# IDC.net
KiCad netlist of a schematic drawn in EAGLE
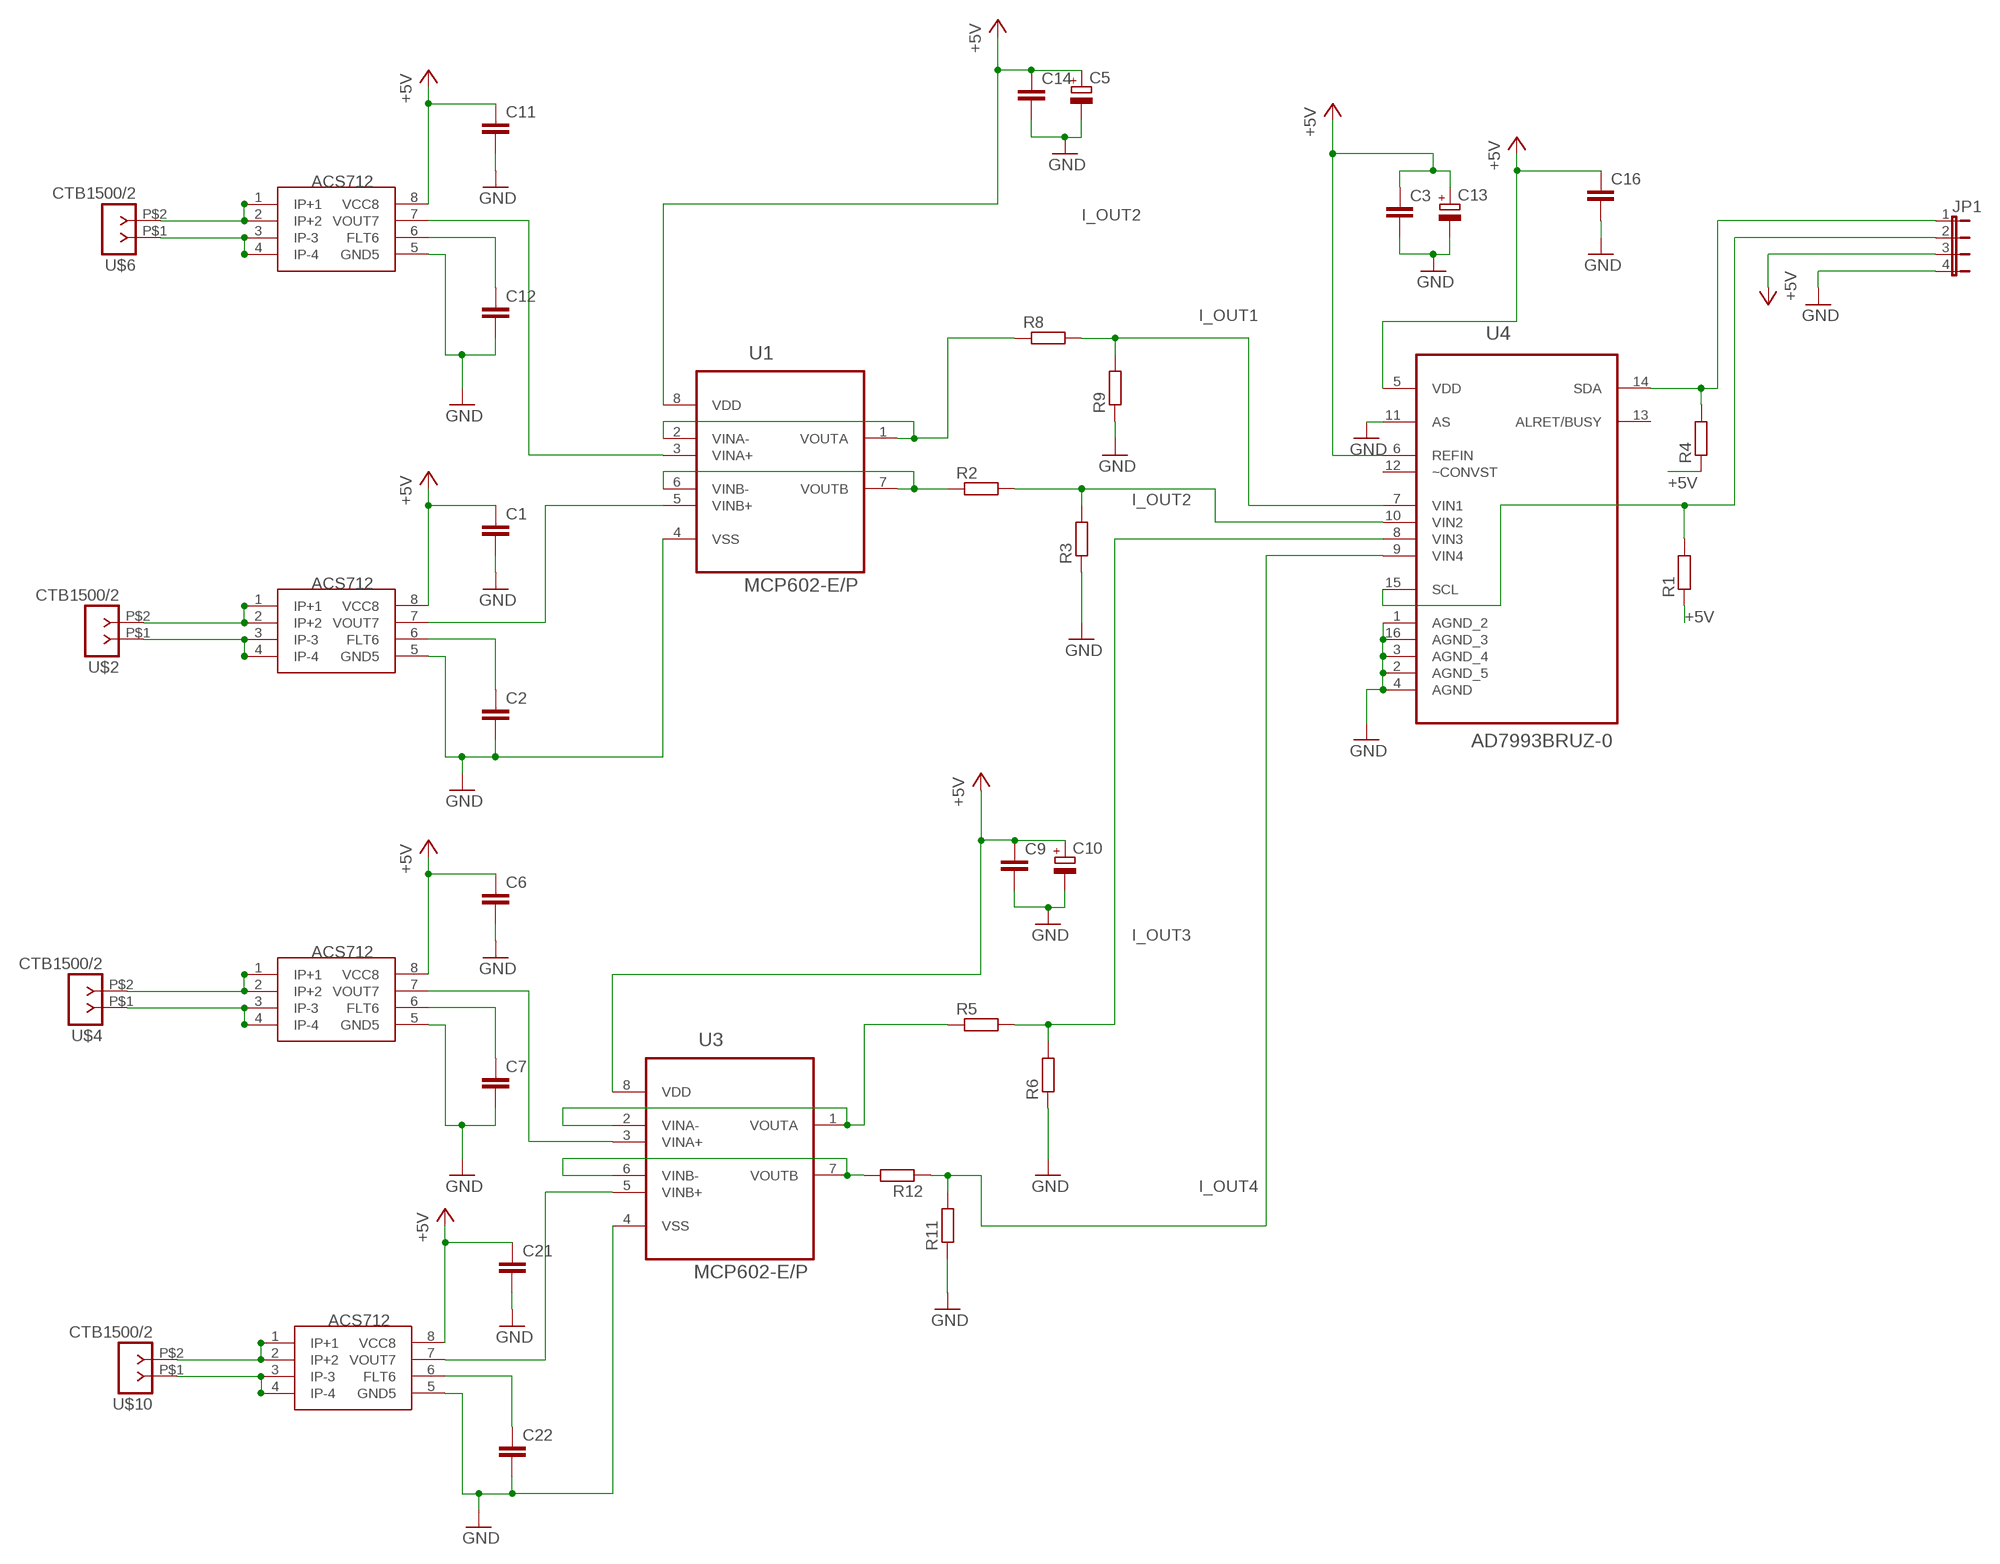
[diagram p0: schematic, sheet 1]

(export (version "E")
  (design (tool "Eeschema 10.0.6"))
  (components
    (comp (ref "C1")
      (value "C-EU025-024X044")
      (footprint "eagle-import:C025-024X044")
      (libsource (lib "eagle-import") (part "C-EU025-024X044"))
    )
    (comp (ref "C2")
      (value "C-EU025-024X044")
      (footprint "eagle-import:C025-024X044")
      (libsource (lib "eagle-import") (part "C-EU025-024X044"))
    )
    (comp (ref "C3")
      (value "C-EU025-024X044")
      (footprint "eagle-import:C025-024X044")
      (libsource (lib "eagle-import") (part "C-EU025-024X044"))
    )
    (comp (ref "C5")
      (value "CPOL-EUE2-4")
      (footprint "eagle-import:E2-4")
      (libsource (lib "eagle-import") (part "CPOL-EUE2-4"))
    )
    (comp (ref "C6")
      (value "C-EU025-024X044")
      (footprint "eagle-import:C025-024X044")
      (libsource (lib "eagle-import") (part "C-EU025-024X044"))
    )
    (comp (ref "C7")
      (value "C-EU025-024X044")
      (footprint "eagle-import:C025-024X044")
      (libsource (lib "eagle-import") (part "C-EU025-024X044"))
    )
    (comp (ref "C9")
      (value "C-EU025-024X044")
      (footprint "eagle-import:C025-024X044")
      (libsource (lib "eagle-import") (part "C-EU025-024X044"))
    )
    (comp (ref "C10")
      (value "CPOL-EUE2-4")
      (footprint "eagle-import:E2-4")
      (libsource (lib "eagle-import") (part "CPOL-EUE2-4"))
    )
    (comp (ref "C11")
      (value "C-EU025-024X044")
      (footprint "eagle-import:C025-024X044")
      (libsource (lib "eagle-import") (part "C-EU025-024X044"))
    )
    (comp (ref "C12")
      (value "C-EU025-024X044")
      (footprint "eagle-import:C025-024X044")
      (libsource (lib "eagle-import") (part "C-EU025-024X044"))
    )
    (comp (ref "C13")
      (value "CPOL-EUE2-4")
      (footprint "eagle-import:E2-4")
      (libsource (lib "eagle-import") (part "CPOL-EUE2-4"))
    )
    (comp (ref "C14")
      (value "C-EU025-024X044")
      (footprint "eagle-import:C025-024X044")
      (libsource (lib "eagle-import") (part "C-EU025-024X044"))
    )
    (comp (ref "C16")
      (value "C-EU025-025X050")
      (footprint "eagle-import:C025-025X050")
      (libsource (lib "eagle-import") (part "C-EU025-025X050"))
    )
    (comp (ref "C21")
      (value "C-EU025-024X044")
      (footprint "eagle-import:C025-024X044")
      (libsource (lib "eagle-import") (part "C-EU025-024X044"))
    )
    (comp (ref "C22")
      (value "C-EU025-024X044")
      (footprint "eagle-import:C025-024X044")
      (libsource (lib "eagle-import") (part "C-EU025-024X044"))
    )
    (comp (ref "JP1")
      (value "JP4E")
      (footprint "eagle-import:JP4")
      (libsource (lib "eagle-import") (part "JP4E"))
    )
    (comp (ref "R1")
      (value "R-EU_0207/7")
      (footprint "eagle-import:0207_7")
      (libsource (lib "eagle-import") (part "R-EU_0207/7"))
    )
    (comp (ref "R2")
      (value "R-EU_0207/7")
      (footprint "eagle-import:0207_7")
      (libsource (lib "eagle-import") (part "R-EU_0207/7"))
    )
    (comp (ref "R3")
      (value "R-EU_0207/7")
      (footprint "eagle-import:0207_7")
      (libsource (lib "eagle-import") (part "R-EU_0207/7"))
    )
    (comp (ref "R4")
      (value "R-EU_0207/7")
      (footprint "eagle-import:0207_7")
      (libsource (lib "eagle-import") (part "R-EU_0207/7"))
    )
    (comp (ref "R5")
      (value "R-EU_0207/7")
      (footprint "eagle-import:0207_7")
      (libsource (lib "eagle-import") (part "R-EU_0207/7"))
    )
    (comp (ref "R6")
      (value "R-EU_0207/7")
      (footprint "eagle-import:0207_7")
      (libsource (lib "eagle-import") (part "R-EU_0207/7"))
    )
    (comp (ref "R8")
      (value "R-EU_0207/7")
      (footprint "eagle-import:0207_7")
      (libsource (lib "eagle-import") (part "R-EU_0207/7"))
    )
    (comp (ref "R9")
      (value "R-EU_0207/7")
      (footprint "eagle-import:0207_7")
      (libsource (lib "eagle-import") (part "R-EU_0207/7"))
    )
    (comp (ref "R11")
      (value "R-EU_0207/7")
      (footprint "eagle-import:0207_7")
      (libsource (lib "eagle-import") (part "R-EU_0207/7"))
    )
    (comp (ref "R12")
      (value "R-EU_0207/7")
      (footprint "eagle-import:0207_7")
      (libsource (lib "eagle-import") (part "R-EU_0207/7"))
    )
    (comp (ref "U$1")
      (value "ACS712")
      (footprint "eagle-import:SO8")
      (libsource (lib "eagle-import") (part "ACS712"))
    )
    (comp (ref "U$2")
      (value "CTB1500/2")
      (footprint "eagle-import:CTB1500-2")
      (libsource (lib "eagle-import") (part "CTB1500/2"))
    )
    (comp (ref "U$3")
      (value "ACS712")
      (footprint "eagle-import:SO8")
      (libsource (lib "eagle-import") (part "ACS712"))
    )
    (comp (ref "U$4")
      (value "CTB1500/2")
      (footprint "eagle-import:CTB1500-2")
      (libsource (lib "eagle-import") (part "CTB1500/2"))
    )
    (comp (ref "U$5")
      (value "ACS712")
      (footprint "eagle-import:SO8")
      (libsource (lib "eagle-import") (part "ACS712"))
    )
    (comp (ref "U$6")
      (value "CTB1500/2")
      (footprint "eagle-import:CTB1500-2")
      (libsource (lib "eagle-import") (part "CTB1500/2"))
    )
    (comp (ref "U$9")
      (value "ACS712")
      (footprint "eagle-import:SO8")
      (libsource (lib "eagle-import") (part "ACS712"))
    )
    (comp (ref "U$10")
      (value "CTB1500/2")
      (footprint "eagle-import:CTB1500-2")
      (libsource (lib "eagle-import") (part "CTB1500/2"))
    )
    (comp (ref "U1")
      (value "MCP602-E/P")
      (footprint "eagle-import:DIP254P762X508-8P")
      (libsource (lib "eagle-import") (part "MCP602-E/P"))
    )
    (comp (ref "U3")
      (value "MCP602-E/P")
      (footprint "eagle-import:DIP254P762X508-8P")
      (libsource (lib "eagle-import") (part "MCP602-E/P"))
    )
    (comp (ref "U4")
      (value "AD7993BRUZ-0")
      (footprint "eagle-import:SOP65P640X120-16N")
      (libsource (lib "eagle-import") (part "AD7993BRUZ-0"))
    )
  )
  (nets
    (net (code "1") (name "+5V") (class "Default")
      (node (ref "C1") (pin "1") (pinfunction "1_1") (pintype "passive"))
      (node (ref "C10") (pin "+") (pinfunction "+_+") (pintype "passive"))
      (node (ref "C11") (pin "1") (pinfunction "1_1") (pintype "passive"))
      (node (ref "C13") (pin "+") (pinfunction "+_+") (pintype "passive"))
      (node (ref "C14") (pin "1") (pinfunction "1_1") (pintype "passive"))
      (node (ref "C16") (pin "1") (pinfunction "1_1") (pintype "passive"))
      (node (ref "C21") (pin "1") (pinfunction "1_1") (pintype "passive"))
      (node (ref "C3") (pin "1") (pinfunction "1_1") (pintype "passive"))
      (node (ref "C5") (pin "+") (pinfunction "+_+") (pintype "passive"))
      (node (ref "C6") (pin "1") (pinfunction "1_1") (pintype "passive"))
      (node (ref "C9") (pin "1") (pinfunction "1_1") (pintype "passive"))
      (node (ref "JP1") (pin "3") (pinfunction "3_3") (pintype "passive"))
      (node (ref "R1") (pin "1") (pinfunction "1_1") (pintype "passive"))
      (node (ref "R4") (pin "1") (pinfunction "1_1") (pintype "passive"))
      (node (ref "U$1") (pin "8") (pinfunction "VCC8_8") (pintype "power_in"))
      (node (ref "U$3") (pin "8") (pinfunction "VCC8_8") (pintype "power_in"))
      (node (ref "U$5") (pin "8") (pinfunction "VCC8_8") (pintype "power_in"))
      (node (ref "U$9") (pin "8") (pinfunction "VCC8_8") (pintype "power_in"))
      (node (ref "U1") (pin "8") (pinfunction "VDD_8") (pintype "power_in"))
      (node (ref "U3") (pin "8") (pinfunction "VDD_8") (pintype "power_in"))
      (node (ref "U4") (pin "5") (pinfunction "VDD_5") (pintype "power_in"))
      (node (ref "U4") (pin "6") (pinfunction "REFIN_6") (pintype "input"))
    )
    (net (code "2") (name "/I_OUT1") (class "Default")
      (node (ref "R8") (pin "2") (pinfunction "2_2") (pintype "passive"))
      (node (ref "R9") (pin "2") (pinfunction "2_2") (pintype "passive"))
      (node (ref "U4") (pin "7") (pinfunction "VIN1_7") (pintype "input"))
    )
    (net (code "3") (name "/I_OUT2") (class "Default")
      (node (ref "R2") (pin "2") (pinfunction "2_2") (pintype "passive"))
      (node (ref "R3") (pin "2") (pinfunction "2_2") (pintype "passive"))
      (node (ref "R8") (pin "1") (pinfunction "1_1") (pintype "passive"))
      (node (ref "U1") (pin "1") (pinfunction "VOUTA_1") (pintype "output"))
      (node (ref "U1") (pin "2") (pinfunction "VINA-_2") (pintype "input"))
      (node (ref "U4") (pin "10") (pinfunction "VIN2_10") (pintype "input"))
    )
    (net (code "4") (name "/I_OUT3") (class "Default")
      (node (ref "R5") (pin "2") (pinfunction "2_2") (pintype "passive"))
      (node (ref "R6") (pin "2") (pinfunction "2_2") (pintype "passive"))
      (node (ref "U4") (pin "8") (pinfunction "VIN3_8") (pintype "input"))
    )
    (net (code "5") (name "/I_OUT4") (class "Default")
      (node (ref "R11") (pin "2") (pinfunction "2_2") (pintype "passive"))
      (node (ref "R12") (pin "1") (pinfunction "1_1") (pintype "passive"))
      (node (ref "U4") (pin "9") (pinfunction "VIN4_9") (pintype "input"))
    )
    (net (code "6") (name "GND") (class "Default")
      (node (ref "C1") (pin "2") (pinfunction "2_2") (pintype "passive"))
      (node (ref "C10") (pin "-") (pinfunction "-_-") (pintype "passive"))
      (node (ref "C11") (pin "2") (pinfunction "2_2") (pintype "passive"))
      (node (ref "C12") (pin "2") (pinfunction "2_2") (pintype "passive"))
      (node (ref "C13") (pin "-") (pinfunction "-_-") (pintype "passive"))
      (node (ref "C14") (pin "2") (pinfunction "2_2") (pintype "passive"))
      (node (ref "C16") (pin "2") (pinfunction "2_2") (pintype "passive"))
      (node (ref "C2") (pin "2") (pinfunction "2_2") (pintype "passive"))
      (node (ref "C21") (pin "2") (pinfunction "2_2") (pintype "passive"))
      (node (ref "C22") (pin "2") (pinfunction "2_2") (pintype "passive"))
      (node (ref "C3") (pin "2") (pinfunction "2_2") (pintype "passive"))
      (node (ref "C5") (pin "-") (pinfunction "-_-") (pintype "passive"))
      (node (ref "C6") (pin "2") (pinfunction "2_2") (pintype "passive"))
      (node (ref "C7") (pin "2") (pinfunction "2_2") (pintype "passive"))
      (node (ref "C9") (pin "2") (pinfunction "2_2") (pintype "passive"))
      (node (ref "JP1") (pin "4") (pinfunction "4_4") (pintype "passive"))
      (node (ref "R11") (pin "1") (pinfunction "1_1") (pintype "passive"))
      (node (ref "R3") (pin "1") (pinfunction "1_1") (pintype "passive"))
      (node (ref "R6") (pin "1") (pinfunction "1_1") (pintype "passive"))
      (node (ref "R9") (pin "1") (pinfunction "1_1") (pintype "passive"))
      (node (ref "U$1") (pin "5") (pinfunction "GND5_5") (pintype "power_in"))
      (node (ref "U$3") (pin "5") (pinfunction "GND5_5") (pintype "power_in"))
      (node (ref "U$5") (pin "5") (pinfunction "GND5_5") (pintype "power_in"))
      (node (ref "U$9") (pin "5") (pinfunction "GND5_5") (pintype "power_in"))
      (node (ref "U1") (pin "4") (pinfunction "VSS_4") (pintype "power_in"))
      (node (ref "U3") (pin "4") (pinfunction "VSS_4") (pintype "power_in"))
      (node (ref "U4") (pin "1") (pinfunction "AGND_2_1") (pintype "passive"))
      (node (ref "U4") (pin "11") (pinfunction "AS_11") (pintype "input"))
      (node (ref "U4") (pin "16") (pinfunction "AGND_3_16") (pintype "passive"))
      (node (ref "U4") (pin "2") (pinfunction "AGND_5_2") (pintype "passive"))
      (node (ref "U4") (pin "3") (pinfunction "AGND_4_3") (pintype "passive"))
      (node (ref "U4") (pin "4") (pinfunction "AGND_4") (pintype "passive"))
    )
    (net (code "7") (name "Net-(U$1-FLT6)") (class "Default")
      (node (ref "C2") (pin "1") (pinfunction "1_1") (pintype "passive"))
      (node (ref "U$1") (pin "6") (pinfunction "FLT6_6") (pintype "passive"))
    )
    (net (code "8") (name "Net-(U$1-IP+1)") (class "Default")
      (node (ref "U$1") (pin "1") (pinfunction "IP+1_1") (pintype "bidirectional"))
      (node (ref "U$1") (pin "2") (pinfunction "IP+2_2") (pintype "bidirectional"))
      (node (ref "U$2") (pin "P$2") (pinfunction "2_P$2") (pintype "passive"))
    )
    (net (code "9") (name "Net-(U$1-IP-3)") (class "Default")
      (node (ref "U$1") (pin "3") (pinfunction "IP-3_3") (pintype "bidirectional"))
      (node (ref "U$1") (pin "4") (pinfunction "IP-4_4") (pintype "bidirectional"))
      (node (ref "U$2") (pin "P$1") (pinfunction "1_P$1") (pintype "passive"))
    )
    (net (code "10") (name "Net-(U$1-VOUT7)") (class "Default")
      (node (ref "U$1") (pin "7") (pinfunction "VOUT7_7") (pintype "output"))
      (node (ref "U1") (pin "5") (pinfunction "VINB+_5") (pintype "input"))
    )
    (net (code "11") (name "Net-(U$3-FLT6)") (class "Default")
      (node (ref "C7") (pin "1") (pinfunction "1_1") (pintype "passive"))
      (node (ref "U$3") (pin "6") (pinfunction "FLT6_6") (pintype "passive"))
    )
    (net (code "12") (name "Net-(U$3-IP+1)") (class "Default")
      (node (ref "U$3") (pin "1") (pinfunction "IP+1_1") (pintype "bidirectional"))
      (node (ref "U$3") (pin "2") (pinfunction "IP+2_2") (pintype "bidirectional"))
      (node (ref "U$4") (pin "P$2") (pinfunction "2_P$2") (pintype "passive"))
    )
    (net (code "13") (name "Net-(U$3-IP-3)") (class "Default")
      (node (ref "U$3") (pin "3") (pinfunction "IP-3_3") (pintype "bidirectional"))
      (node (ref "U$3") (pin "4") (pinfunction "IP-4_4") (pintype "bidirectional"))
      (node (ref "U$4") (pin "P$1") (pinfunction "1_P$1") (pintype "passive"))
    )
    (net (code "14") (name "Net-(U$3-VOUT7)") (class "Default")
      (node (ref "U$3") (pin "7") (pinfunction "VOUT7_7") (pintype "output"))
      (node (ref "U3") (pin "3") (pinfunction "VINA+_3") (pintype "input"))
    )
    (net (code "15") (name "Net-(U$5-FLT6)") (class "Default")
      (node (ref "C12") (pin "1") (pinfunction "1_1") (pintype "passive"))
      (node (ref "U$5") (pin "6") (pinfunction "FLT6_6") (pintype "passive"))
    )
    (net (code "16") (name "Net-(U$5-IP+1)") (class "Default")
      (node (ref "U$5") (pin "1") (pinfunction "IP+1_1") (pintype "bidirectional"))
      (node (ref "U$5") (pin "2") (pinfunction "IP+2_2") (pintype "bidirectional"))
      (node (ref "U$6") (pin "P$2") (pinfunction "2_P$2") (pintype "passive"))
    )
    (net (code "17") (name "Net-(U$5-IP-3)") (class "Default")
      (node (ref "U$5") (pin "3") (pinfunction "IP-3_3") (pintype "bidirectional"))
      (node (ref "U$5") (pin "4") (pinfunction "IP-4_4") (pintype "bidirectional"))
      (node (ref "U$6") (pin "P$1") (pinfunction "1_P$1") (pintype "passive"))
    )
    (net (code "18") (name "Net-(U$5-VOUT7)") (class "Default")
      (node (ref "U$5") (pin "7") (pinfunction "VOUT7_7") (pintype "output"))
      (node (ref "U1") (pin "3") (pinfunction "VINA+_3") (pintype "input"))
    )
    (net (code "19") (name "Net-(U$9-FLT6)") (class "Default")
      (node (ref "C22") (pin "1") (pinfunction "1_1") (pintype "passive"))
      (node (ref "U$9") (pin "6") (pinfunction "FLT6_6") (pintype "passive"))
    )
    (net (code "20") (name "Net-(U$9-VOUT7)") (class "Default")
      (node (ref "U$9") (pin "7") (pinfunction "VOUT7_7") (pintype "output"))
      (node (ref "U3") (pin "5") (pinfunction "VINB+_5") (pintype "input"))
    )
    (net (code "21") (name "Net-(U$10-1)") (class "Default")
      (node (ref "U$10") (pin "P$1") (pinfunction "1_P$1") (pintype "passive"))
      (node (ref "U$9") (pin "3") (pinfunction "IP-3_3") (pintype "bidirectional"))
      (node (ref "U$9") (pin "4") (pinfunction "IP-4_4") (pintype "bidirectional"))
    )
    (net (code "22") (name "Net-(U$10-2)") (class "Default")
      (node (ref "U$10") (pin "P$2") (pinfunction "2_P$2") (pintype "passive"))
      (node (ref "U$9") (pin "1") (pinfunction "IP+1_1") (pintype "bidirectional"))
      (node (ref "U$9") (pin "2") (pinfunction "IP+2_2") (pintype "bidirectional"))
    )
    (net (code "23") (name "Net-(U1-VINB-)") (class "Default")
      (node (ref "R2") (pin "1") (pinfunction "1_1") (pintype "passive"))
      (node (ref "U1") (pin "6") (pinfunction "VINB-_6") (pintype "input"))
      (node (ref "U1") (pin "7") (pinfunction "VOUTB_7") (pintype "output"))
    )
    (net (code "24") (name "Net-(U3-VINA-)") (class "Default")
      (node (ref "R5") (pin "1") (pinfunction "1_1") (pintype "passive"))
      (node (ref "U3") (pin "1") (pinfunction "VOUTA_1") (pintype "output"))
      (node (ref "U3") (pin "2") (pinfunction "VINA-_2") (pintype "input"))
    )
    (net (code "25") (name "Net-(U3-VINB-)") (class "Default")
      (node (ref "R12") (pin "2") (pinfunction "2_2") (pintype "passive"))
      (node (ref "U3") (pin "6") (pinfunction "VINB-_6") (pintype "input"))
      (node (ref "U3") (pin "7") (pinfunction "VOUTB_7") (pintype "output"))
    )
    (net (code "26") (name "Net-(U4-SCL)") (class "Default")
      (node (ref "JP1") (pin "2") (pinfunction "2_2") (pintype "passive"))
      (node (ref "R1") (pin "2") (pinfunction "2_2") (pintype "passive"))
      (node (ref "U4") (pin "15") (pinfunction "SCL_15") (pintype "input"))
    )
    (net (code "27") (name "Net-(U4-SDA)") (class "Default")
      (node (ref "JP1") (pin "1") (pinfunction "1_1") (pintype "passive"))
      (node (ref "R4") (pin "2") (pinfunction "2_2") (pintype "passive"))
      (node (ref "U4") (pin "14") (pinfunction "SDA_14") (pintype "bidirectional"))
    )
    (net (code "28") (name "unconnected-(U4-ALRET{slash}BUSY-Pad13)") (class "Default")
      (node (ref "U4") (pin "13") (pinfunction "ALRET/BUSY_13") (pintype "output"))
    )
    (net (code "29") (name "unconnected-(U4-~{CONVST}-Pad12)") (class "Default")
      (node (ref "U4") (pin "12") (pinfunction "~{CONVST}_12") (pintype "input"))
    )
  )
)
